# spindle_controller.net
KiCad netlist of a schematic drawn in EAGLE
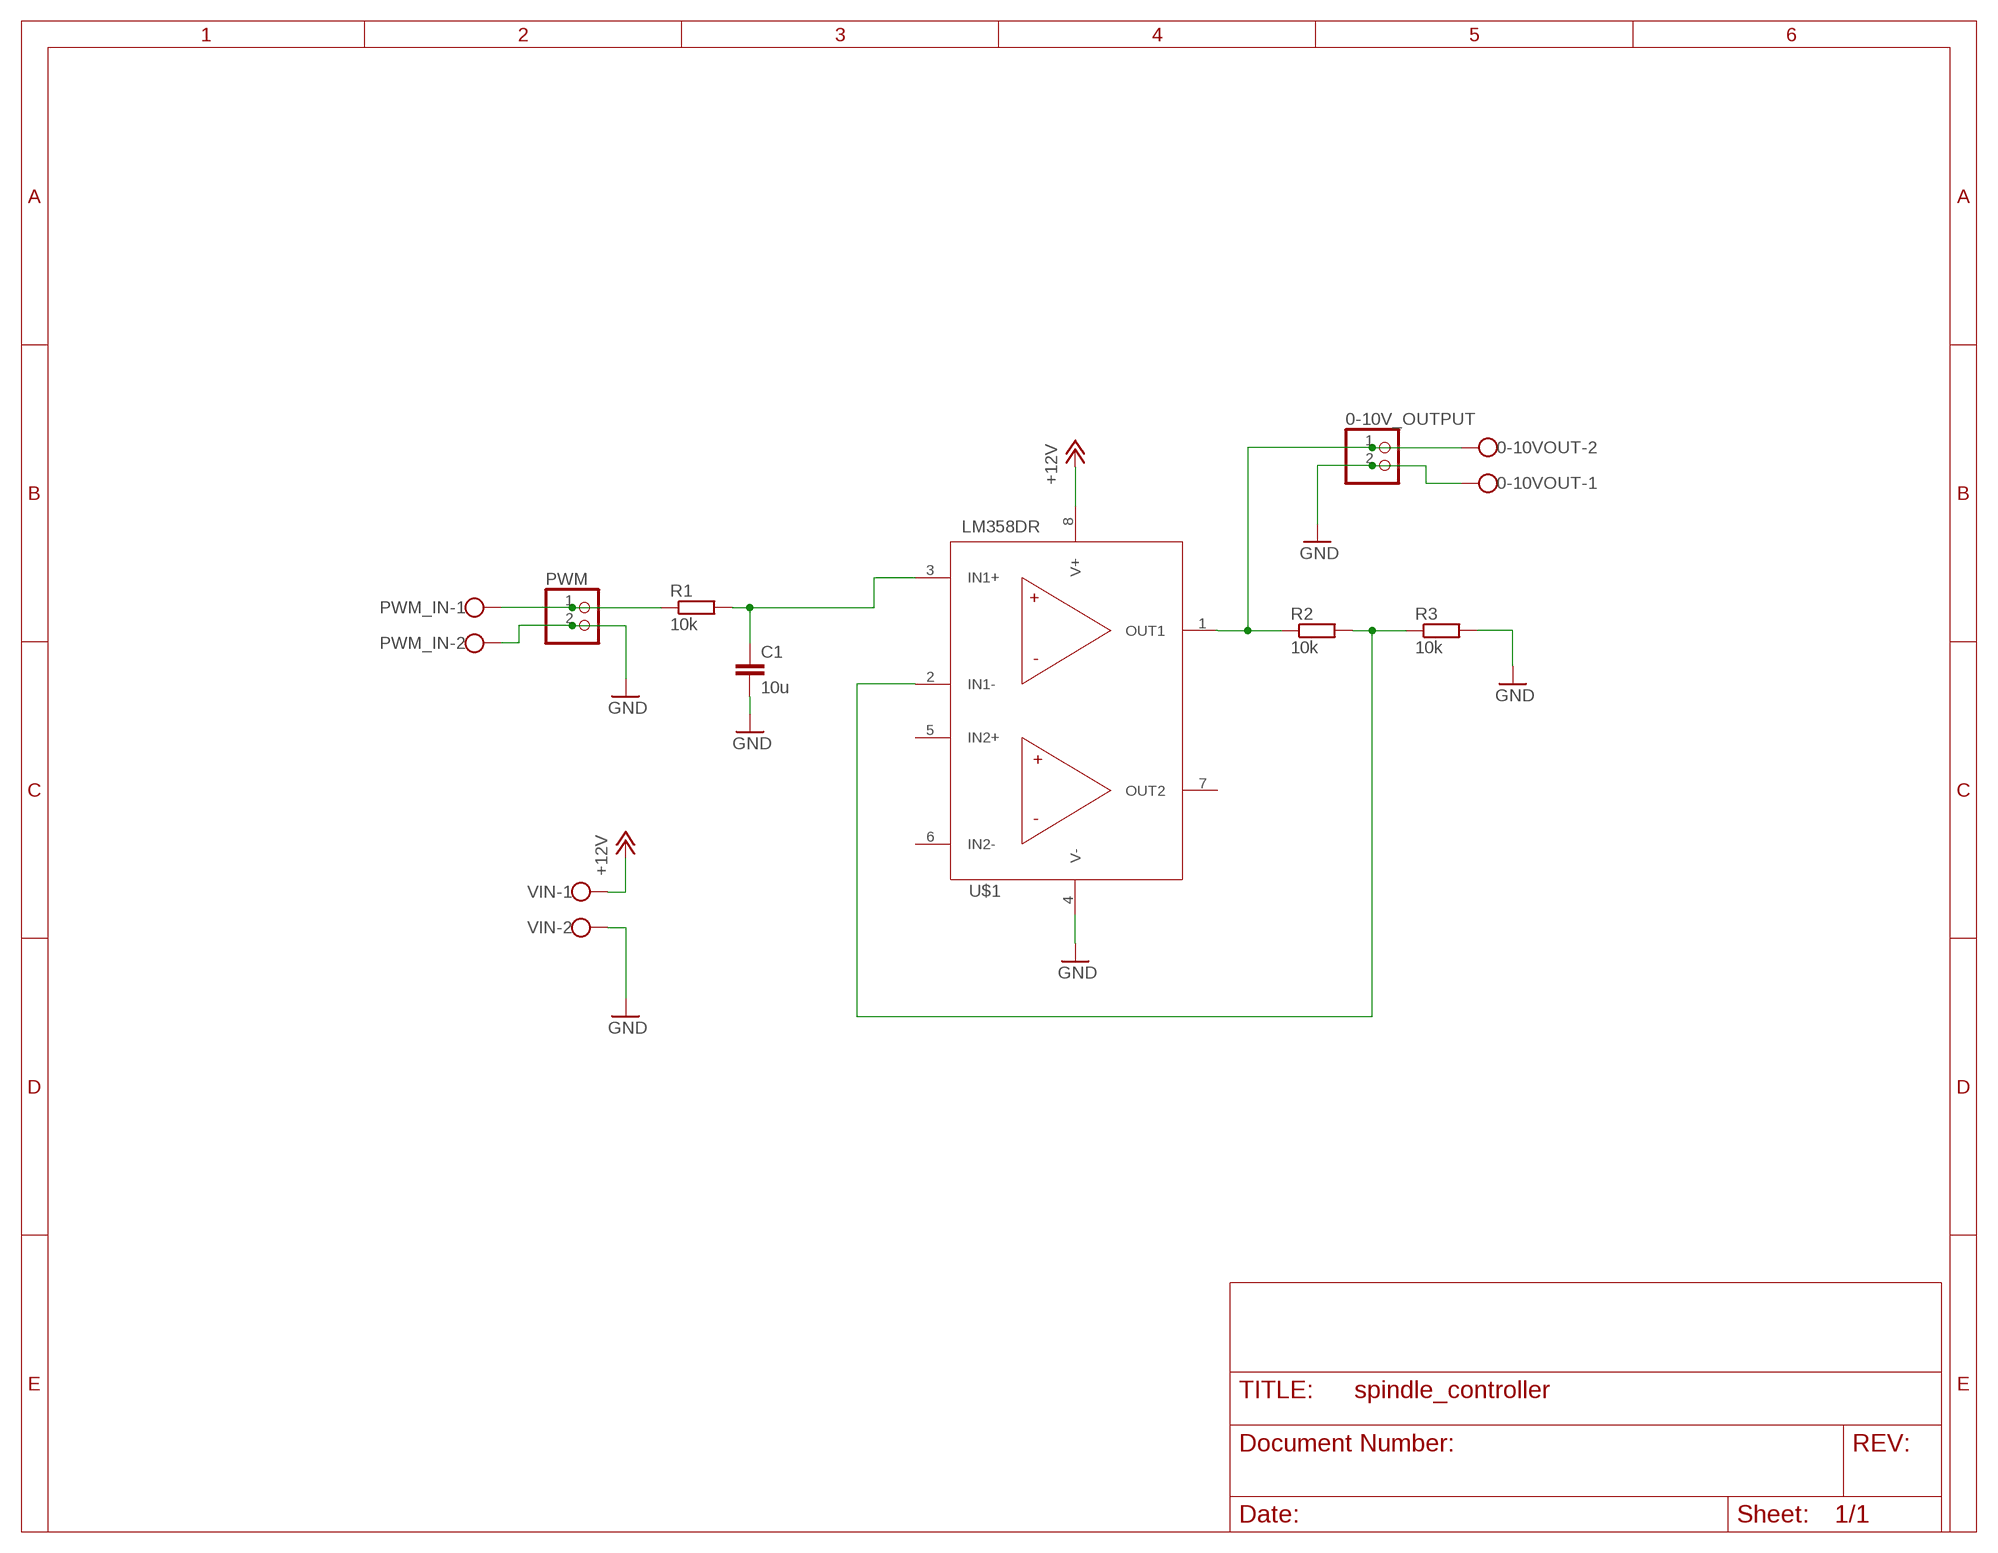
[diagram p0: schematic, sheet 1]

(export (version "E")
  (design (tool "Eeschema 10.0.6"))
  (components
    (comp (ref "0-10VOUT")
      (value "W237-102")
      (footprint "eagle-import:W237-102")
      (fields (field (name "MPN") "237-102"))
      (libsource (lib "eagle-import") (part "W237-102"))
    )
    (comp (ref "0-10V_OUTPUT")
      (value "PINHD-1X2")
      (footprint "eagle-import:1X02")
      (libsource (lib "eagle-import") (part "PINHD-1X2"))
    )
    (comp (ref "C1")
      (value "10u")
      (footprint "eagle-import:C0603")
      (libsource (lib "eagle-import") (part "C-EUC0603"))
    )
    (comp (ref "PWM")
      (value "PINHD-1X2")
      (footprint "eagle-import:1X02")
      (libsource (lib "eagle-import") (part "PINHD-1X2"))
    )
    (comp (ref "PWM_IN")
      (value "W237-102")
      (footprint "eagle-import:W237-102")
      (fields (field (name "MPN") "237-102"))
      (libsource (lib "eagle-import") (part "W237-102"))
    )
    (comp (ref "R1")
      (value "10k")
      (footprint "eagle-import:R0603")
      (libsource (lib "eagle-import") (part "R-EU_R0603"))
    )
    (comp (ref "R2")
      (value "10k")
      (footprint "eagle-import:R0603")
      (libsource (lib "eagle-import") (part "R-EU_R0603"))
    )
    (comp (ref "R3")
      (value "10k")
      (footprint "eagle-import:R0603")
      (libsource (lib "eagle-import") (part "R-EU_R0603"))
    )
    (comp (ref "U$1")
      (value "LM358DRLM358DR_SOIC8")
      (footprint "eagle-import:SOIC127P599X175-8N")
      (libsource (lib "eagle-import") (part "LM358DRLM358DR_SOIC8"))
    )
    (comp (ref "VIN")
      (value "W237-102")
      (footprint "eagle-import:W237-102")
      (fields (field (name "MPN") "237-102"))
      (libsource (lib "eagle-import") (part "W237-102"))
    )
  )
  (nets
    (net (code "1") (name "+12V") (class "Default")
      (node (ref "U$1") (pin "8") (pinfunction "V+_8") (pintype "bidirectional"))
      (node (ref "VIN") (pin "1") (pinfunction "KL_1") (pintype "passive"))
    )
    (net (code "2") (name "GND") (class "Default")
      (node (ref "0-10VOUT") (pin "1") (pinfunction "KL_1") (pintype "passive"))
      (node (ref "0-10V_OUTPUT") (pin "2") (pinfunction "2_2") (pintype "passive"))
      (node (ref "C1") (pin "2") (pinfunction "2_2") (pintype "passive"))
      (node (ref "PWM") (pin "2") (pinfunction "2_2") (pintype "passive"))
      (node (ref "PWM_IN") (pin "2") (pinfunction "KL_2") (pintype "passive"))
      (node (ref "R3") (pin "2") (pinfunction "2_2") (pintype "passive"))
      (node (ref "U$1") (pin "4") (pinfunction "V-_4") (pintype "bidirectional"))
      (node (ref "VIN") (pin "2") (pinfunction "KL_2") (pintype "passive"))
    )
    (net (code "3") (name "Net-(0-10VOUTB-KL)") (class "Default")
      (node (ref "0-10VOUT") (pin "2") (pinfunction "KL_2") (pintype "passive"))
      (node (ref "0-10V_OUTPUT") (pin "1") (pinfunction "1_1") (pintype "passive"))
      (node (ref "R2") (pin "1") (pinfunction "1_1") (pintype "passive"))
      (node (ref "U$1") (pin "1") (pinfunction "OUT1_1") (pintype "bidirectional"))
    )
    (net (code "4") (name "Net-(PWM_INA-KL)") (class "Default")
      (node (ref "PWM") (pin "1") (pinfunction "1_1") (pintype "passive"))
      (node (ref "PWM_IN") (pin "1") (pinfunction "KL_1") (pintype "passive"))
      (node (ref "R1") (pin "1") (pinfunction "1_1") (pintype "passive"))
    )
    (net (code "5") (name "Net-(U$1-IN1+)") (class "Default")
      (node (ref "C1") (pin "1") (pinfunction "1_1") (pintype "passive"))
      (node (ref "R1") (pin "2") (pinfunction "2_2") (pintype "passive"))
      (node (ref "U$1") (pin "3") (pinfunction "IN1+_3") (pintype "bidirectional"))
    )
    (net (code "6") (name "Net-(U$1-IN1-)") (class "Default")
      (node (ref "R2") (pin "2") (pinfunction "2_2") (pintype "passive"))
      (node (ref "R3") (pin "1") (pinfunction "1_1") (pintype "passive"))
      (node (ref "U$1") (pin "2") (pinfunction "IN1-_2") (pintype "bidirectional"))
    )
    (net (code "7") (name "unconnected-(U$1-IN2+-Pad5)") (class "Default")
      (node (ref "U$1") (pin "5") (pinfunction "IN2+_5") (pintype "bidirectional"))
    )
    (net (code "8") (name "unconnected-(U$1-IN2--Pad6)") (class "Default")
      (node (ref "U$1") (pin "6") (pinfunction "IN2-_6") (pintype "bidirectional"))
    )
    (net (code "9") (name "unconnected-(U$1-OUT2-Pad7)") (class "Default")
      (node (ref "U$1") (pin "7") (pinfunction "OUT2_7") (pintype "bidirectional"))
    )
  )
)
